# step_up_down.net
KiCad netlist of a schematic drawn in Altium Designer
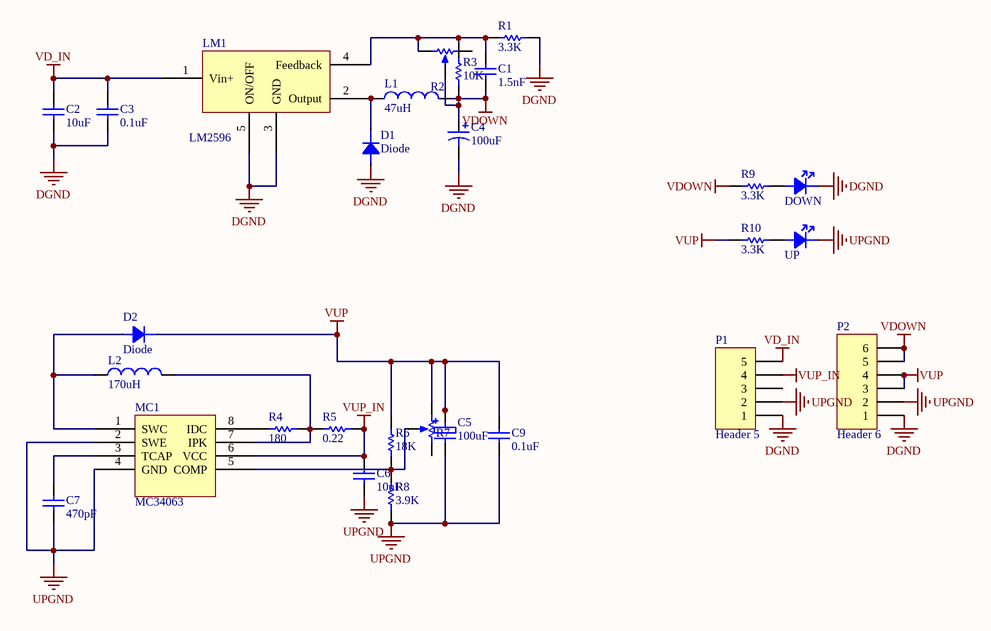
[diagram p0: step_up_down.SchDoc]

(export (version "E")
  (design (tool "Eeschema 10.0.6"))
  (components
    (comp (ref "C1")
      (value "1.5nF")
      (footprint "CAP-MLCC-0603")
      (description "Capacitor")
      (fields (field (name "Comment") "Cap") (field (name "PUBLISHER") "Altium Limited"))
      (libsource (lib "K60-mainboard-v3.1") (part "Cap"))
    )
    (comp (ref "C2")
      (value "10uF")
      (footprint "0805C")
      (description "Capacitor")
      (fields (field (name "Comment") "Cap") (field (name "PUBLISHER") "Altium Limited"))
      (libsource (lib "K60-mainboard-v3.1") (part "Cap"))
    )
    (comp (ref "C3")
      (value "0.1uF")
      (footprint "CAP-MLCC-0603")
      (description "Capacitor")
      (fields (field (name "Comment") "Cap") (field (name "PUBLISHER") "Altium Limited"))
      (libsource (lib "K60-mainboard-v3.1") (part "Cap"))
    )
    (comp (ref "C4")
      (value "100uF")
      (footprint "6032C")
      (description "Polarized Capacitor (Surface Mount)")
      (fields (field (name "Comment") "Cap Pol3") (field (name "PUBLISHER") "Altium Limited"))
      (libsource (lib "K60-mainboard-v3.1") (part "Cap Pol3"))
    )
    (comp (ref "C5")
      (value "100uF")
      (footprint "C_ELE")
      (description "电解电容")
      (fields (field (name "PUBLISHER") "Altium Limited"))
      (libsource (lib "Libraries_2014_0618") (part "CAP-ELE"))
    )
    (comp (ref "C6")
      (value "10uF")
      (footprint "0805C")
      (description "Capacitor")
      (fields (field (name "Comment") "Cap") (field (name "PUBLISHER") "Altium Limited"))
      (libsource (lib "K60-mainboard-v3.1") (part "Cap"))
    )
    (comp (ref "C7")
      (value "470pF")
      (footprint "CAP-MLCC-0603")
      (description "Capacitor")
      (fields (field (name "Comment") "Cap") (field (name "PUBLISHER") "Altium Limited"))
      (libsource (lib "K60-mainboard-v3.1") (part "Cap"))
    )
    (comp (ref "C9")
      (value "0.1uF")
      (footprint "CAP-MLCC-0603")
      (description "Capacitor")
      (fields (field (name "Comment") "Cap") (field (name "PUBLISHER") "Altium Limited"))
      (libsource (lib "K60-mainboard-v3.1") (part "Cap"))
    )
    (comp (ref "D1") (value "Diode") (footprint "SS34") (libsource (lib "K60-mainboard-v3.1") (part "Diode")))
    (comp (ref "D2") (value "Diode") (footprint "SS34") (libsource (lib "K60-mainboard-v3.1") (part "Diode")))
    (comp (ref "DOWN")
      (value "lED")
      (footprint "0805D")
      (description "LED")
      (libsource (lib "K60-mainboard-v3.1") (part "00-D-LED"))
    )
    (comp (ref "L1")
      (value "47uH")
      (footprint "CD74")
      (description "Inductor")
      (fields (field (name "PUBLISHER") "Altium Limited"))
      (libsource (lib "smartcar_example") (part "Inductor"))
    )
    (comp (ref "L2")
      (value "170uH")
      (footprint "CD74")
      (description "Inductor")
      (fields (field (name "PUBLISHER") "Altium Limited"))
      (libsource (lib "smartcar_example") (part "Inductor"))
    )
    (comp (ref "LM1")
      (value "LM2596")
      (footprint "TO-263-5")
      (description "12-5")
      (libsource (lib "Libraries_2014_0618") (part "LM2596"))
    )
    (comp (ref "MC1")
      (value "MC34063")
      (footprint "LT1963-SOP8")
      (libsource (lib "K60-mainboard-v3.1") (part "MC34063"))
    )
    (comp (ref "P1")
      (value "Header 5")
      (footprint "HDR1X5")
      (description "Header, 5-Pin")
      (fields (field (name "PUBLISHER") "Altium Limited"))
      (libsource (lib "K60-mainboard-v3.1") (part "Header 5"))
    )
    (comp (ref "P2")
      (value "Header 6")
      (footprint "HDR1X6")
      (description "Header, 6-Pin")
      (fields (field (name "PUBLISHER") "Altium Limited"))
      (libsource (lib "K60-mainboard-v3.1") (part "Header 6"))
    )
    (comp (ref "R1")
      (value "3.3K")
      (footprint "RES-0603")
      (description "Resistor")
      (fields (field (name "Comment") "Res1") (field (name "PUBLISHER") "Altium Limited"))
      (libsource (lib "K60-mainboard-v3.1") (part "Res1"))
    )
    (comp (ref "R2")
      (value "RPot")
      (footprint "VR5")
      (description "Potentiometer")
      (fields (field (name "PUBLISHER") "Altium Limited"))
      (libsource (lib "smartcar_example") (part "RPot"))
    )
    (comp (ref "R3")
      (value "10K")
      (footprint "RES-0603")
      (description "Resistor")
      (fields (field (name "Comment") "Res1") (field (name "PUBLISHER") "Altium Limited"))
      (libsource (lib "K60-mainboard-v3.1") (part "Res1"))
    )
    (comp (ref "R4")
      (value "180")
      (footprint "RES-0603")
      (description "Resistor")
      (fields (field (name "Comment") "Res1") (field (name "PUBLISHER") "Altium Limited"))
      (libsource (lib "K60-mainboard-v3.1") (part "Res1"))
    )
    (comp (ref "R5")
      (value "0.22")
      (footprint "RES-0603")
      (description "Resistor")
      (fields (field (name "Comment") "Res1") (field (name "PUBLISHER") "Altium Limited"))
      (libsource (lib "K60-mainboard-v3.1") (part "Res1"))
    )
    (comp (ref "R6")
      (value "18K")
      (footprint "RES-0603")
      (description "Resistor")
      (fields (field (name "Comment") "Res1") (field (name "PUBLISHER") "Altium Limited"))
      (libsource (lib "K60-mainboard-v3.1") (part "Res1"))
    )
    (comp (ref "R7")
      (value "RPot")
      (footprint "VR5")
      (description "Potentiometer")
      (fields (field (name "PUBLISHER") "Altium Limited"))
      (libsource (lib "smartcar_example") (part "RPot"))
    )
    (comp (ref "R8")
      (value "3.9K")
      (footprint "RES-0603")
      (description "Resistor")
      (fields (field (name "Comment") "Res1") (field (name "PUBLISHER") "Altium Limited"))
      (libsource (lib "K60-mainboard-v3.1") (part "Res1"))
    )
    (comp (ref "R9")
      (value "3.3K")
      (footprint "RES-0603")
      (description "Resistor")
      (fields (field (name "Comment") "Res1") (field (name "PUBLISHER") "Altium Limited"))
      (libsource (lib "K60-mainboard-v3.1") (part "Res1"))
    )
    (comp (ref "R10")
      (value "3.3K")
      (footprint "RES-0603")
      (description "Resistor")
      (fields (field (name "Comment") "Res1") (field (name "PUBLISHER") "Altium Limited"))
      (libsource (lib "K60-mainboard-v3.1") (part "Res1"))
    )
    (comp (ref "UP")
      (value "lED")
      (footprint "0805D")
      (description "LED")
      (libsource (lib "K60-mainboard-v3.1") (part "00-D-LED"))
    )
  )
  (nets
    (net (code "1") (name "DGND") (class "Default")
      (node (ref "C2") (pin "1") (pinfunction "1_1") (pintype "passive"))
      (node (ref "C3") (pin "1") (pinfunction "1_1") (pintype "passive"))
      (node (ref "C4") (pin "2") (pinfunction "2_2") (pintype "passive"))
      (node (ref "D1") (pin "A") (pinfunction "1_A") (pintype "passive"))
      (node (ref "DOWN") (pin "K") (pinfunction "2_K") (pintype "passive"))
      (node (ref "LM1") (pin "3") (pinfunction "GND_3") (pintype "passive"))
      (node (ref "LM1") (pin "5") (pinfunction "ON/OFF_5") (pintype "passive"))
      (node (ref "P1") (pin "1") (pinfunction "1_1") (pintype "passive"))
      (node (ref "P2") (pin "1") (pinfunction "1_1") (pintype "passive"))
      (node (ref "R1") (pin "1") (pinfunction "1_1") (pintype "passive"))
    )
    (net (code "2") (name "Net-(D1-2)") (class "Default")
      (node (ref "D1") (pin "K") (pinfunction "2_K") (pintype "passive"))
      (node (ref "L1") (pin "1") (pinfunction "1_1") (pintype "passive"))
      (node (ref "LM1") (pin "2") (pinfunction "Output_2") (pintype "passive"))
    )
    (net (code "3") (name "Net-(D2-1)") (class "Default")
      (node (ref "D2") (pin "A") (pinfunction "1_A") (pintype "passive"))
      (node (ref "L2") (pin "1") (pinfunction "1_1") (pintype "passive"))
      (node (ref "MC1") (pin "1") (pinfunction "SWC_1") (pintype "passive"))
    )
    (net (code "4") (name "Net-(DOWN-1)") (class "Default")
      (node (ref "DOWN") (pin "A") (pinfunction "1_A") (pintype "passive"))
      (node (ref "R9") (pin "1") (pinfunction "1_1") (pintype "passive"))
    )
    (net (code "5") (name "Net-(LM1-Feedback)") (class "Default")
      (node (ref "C1") (pin "2") (pinfunction "2_2") (pintype "passive"))
      (node (ref "LM1") (pin "4") (pinfunction "Feedback_4") (pintype "passive"))
      (node (ref "R1") (pin "2") (pinfunction "2_2") (pintype "passive"))
      (node (ref "R2") (pin "1") (pinfunction "TOP_1") (pintype "passive"))
      (node (ref "R3") (pin "2") (pinfunction "2_2") (pintype "passive"))
    )
    (net (code "6") (name "Net-(MC1-COMP)") (class "Default")
      (node (ref "MC1") (pin "5") (pinfunction "COMP_5") (pintype "passive"))
      (node (ref "R6") (pin "2") (pinfunction "2_2") (pintype "passive"))
      (node (ref "R7") (pin "2") (pinfunction "TAP_2") (pintype "passive"))
      (node (ref "R8") (pin "1") (pinfunction "1_1") (pintype "passive"))
    )
    (net (code "7") (name "Net-(MC1-IDC)") (class "Default")
      (node (ref "MC1") (pin "8") (pinfunction "IDC_8") (pintype "passive"))
      (node (ref "R4") (pin "2") (pinfunction "2_2") (pintype "passive"))
    )
    (net (code "8") (name "Net-(MC1-IPK)") (class "Default")
      (node (ref "L2") (pin "2") (pinfunction "2_2") (pintype "passive"))
      (node (ref "MC1") (pin "7") (pinfunction "IPK_7") (pintype "passive"))
      (node (ref "R4") (pin "1") (pinfunction "1_1") (pintype "passive"))
      (node (ref "R5") (pin "2") (pinfunction "2_2") (pintype "passive"))
    )
    (net (code "9") (name "Net-(MC1-TCAP)") (class "Default")
      (node (ref "C7") (pin "2") (pinfunction "2_2") (pintype "passive"))
      (node (ref "MC1") (pin "3") (pinfunction "TCAP_3") (pintype "passive"))
    )
    (net (code "10") (name "Net-(UP-1)") (class "Default")
      (node (ref "R10") (pin "1") (pinfunction "1_1") (pintype "passive"))
      (node (ref "UP") (pin "A") (pinfunction "1_A") (pintype "passive"))
    )
    (net (code "11") (name "UPGND") (class "Default")
      (node (ref "C5") (pin "2") (pinfunction "2_2") (pintype "passive"))
      (node (ref "C6") (pin "1") (pinfunction "1_1") (pintype "passive"))
      (node (ref "C7") (pin "1") (pinfunction "1_1") (pintype "passive"))
      (node (ref "C9") (pin "1") (pinfunction "1_1") (pintype "passive"))
      (node (ref "MC1") (pin "2") (pinfunction "SWE_2") (pintype "passive"))
      (node (ref "MC1") (pin "4") (pinfunction "GND_4") (pintype "passive"))
      (node (ref "P1") (pin "2") (pinfunction "2_2") (pintype "passive"))
      (node (ref "P2") (pin "2") (pinfunction "2_2") (pintype "passive"))
      (node (ref "R8") (pin "2") (pinfunction "2_2") (pintype "passive"))
      (node (ref "UP") (pin "K") (pinfunction "2_K") (pintype "passive"))
    )
    (net (code "12") (name "VDOWN") (class "Default")
      (node (ref "C1") (pin "1") (pinfunction "1_1") (pintype "passive"))
      (node (ref "C4") (pin "1") (pinfunction "1_1") (pintype "passive"))
      (node (ref "L1") (pin "2") (pinfunction "2_2") (pintype "passive"))
      (node (ref "P2") (pin "5") (pinfunction "5_5") (pintype "passive"))
      (node (ref "P2") (pin "6") (pinfunction "6_6") (pintype "passive"))
      (node (ref "R2") (pin "2") (pinfunction "TAP_2") (pintype "passive"))
      (node (ref "R3") (pin "1") (pinfunction "1_1") (pintype "passive"))
      (node (ref "R9") (pin "2") (pinfunction "2_2") (pintype "passive"))
    )
    (net (code "13") (name "VD_IN") (class "Default")
      (node (ref "C2") (pin "2") (pinfunction "2_2") (pintype "passive"))
      (node (ref "C3") (pin "2") (pinfunction "2_2") (pintype "passive"))
      (node (ref "LM1") (pin "1") (pinfunction "Vin+_1") (pintype "passive"))
      (node (ref "P1") (pin "5") (pinfunction "5_5") (pintype "passive"))
    )
    (net (code "14") (name "VUP") (class "Default")
      (node (ref "C5") (pin "1") (pinfunction "1_1") (pintype "passive"))
      (node (ref "C9") (pin "2") (pinfunction "2_2") (pintype "passive"))
      (node (ref "D2") (pin "K") (pinfunction "2_K") (pintype "passive"))
      (node (ref "P2") (pin "3") (pinfunction "3_3") (pintype "passive"))
      (node (ref "P2") (pin "4") (pinfunction "4_4") (pintype "passive"))
      (node (ref "R10") (pin "2") (pinfunction "2_2") (pintype "passive"))
      (node (ref "R6") (pin "1") (pinfunction "1_1") (pintype "passive"))
      (node (ref "R7") (pin "1") (pinfunction "TOP_1") (pintype "passive"))
    )
    (net (code "15") (name "VUP_IN") (class "Default")
      (node (ref "C6") (pin "2") (pinfunction "2_2") (pintype "passive"))
      (node (ref "MC1") (pin "6") (pinfunction "VCC_6") (pintype "passive"))
      (node (ref "P1") (pin "4") (pinfunction "4_4") (pintype "passive"))
      (node (ref "R5") (pin "1") (pinfunction "1_1") (pintype "passive"))
    )
    (net (code "16") (name "unconnected-(P1-Pad3)") (class "Default")
      (node (ref "P1") (pin "3") (pinfunction "3_3") (pintype "passive"))
    )
    (net (code "17") (name "unconnected-(R2-BOT-Pad3)") (class "Default")
      (node (ref "R2") (pin "3") (pinfunction "BOT_3") (pintype "passive"))
    )
    (net (code "18") (name "unconnected-(R7-BOT-Pad3)") (class "Default")
      (node (ref "R7") (pin "3") (pinfunction "BOT_3") (pintype "passive"))
    )
  )
)
